# 1-Schematic_FFF_PCB_Connector.net
KiCad netlist of a schematic drawn in EasyEDA
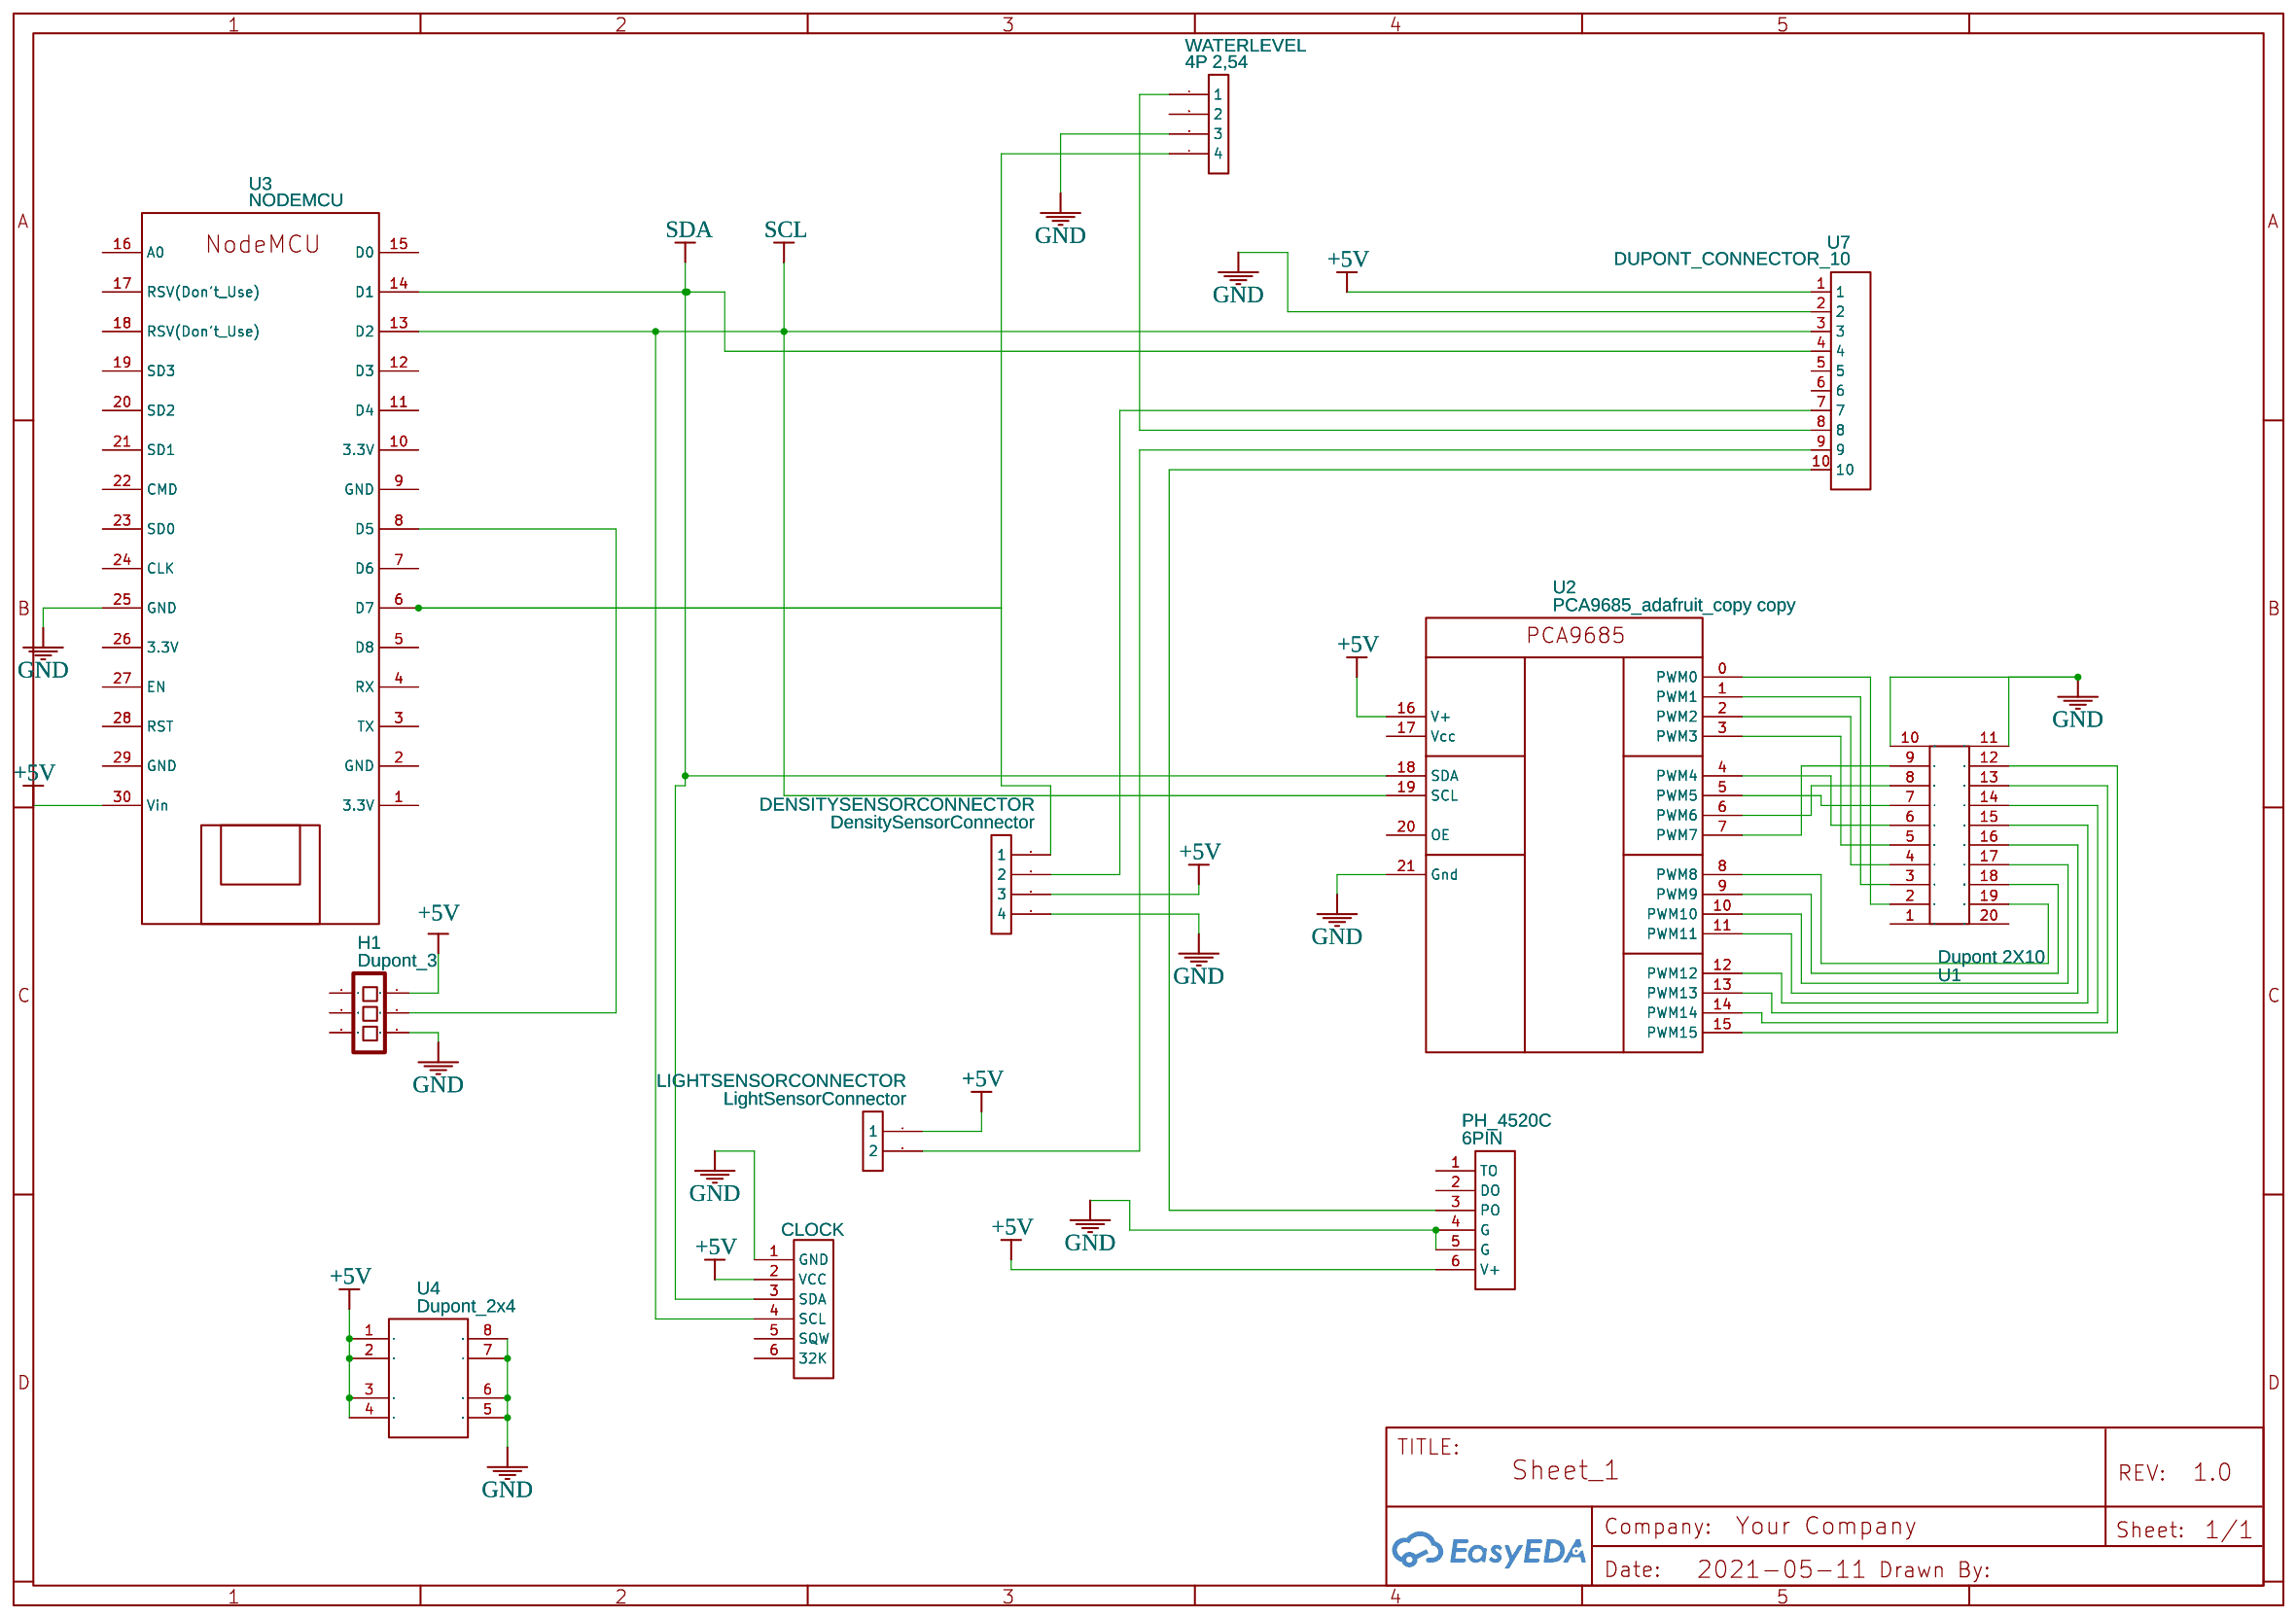
[diagram p0: schematic sheet]

(export (version "E")
  (design (tool "Eeschema 10.0.6"))
  (components
    (comp (ref "CLOCK") (value "6PIN") (libsource (lib "") (part "6PIN_1")))
    (comp (ref "DENSITYSENSORCONNECTOR")
      (value "DensitySensorConnector")
      (fields (field (name "BOM_Manufacturer Part") "Conector_dupont"))
      (libsource (lib "") (part "4P 2,54"))
    )
    (comp (ref "H1") (value "Dupont_3") (libsource (lib "") (part "Dupont_3")))
    (comp (ref "LIGHTSENSORCONNECTOR")
      (value "LightSensorConnector")
      (fields (field (name "BOM_Manufacturer Part") "Conector_dupont"))
      (libsource (lib "") (part "Dupont_1x2"))
    )
    (comp (ref "PH_4520C") (value "6PIN") (libsource (lib "") (part "6PIN")))
    (comp (ref "U1") (value "Dupont 2X10") (libsource (lib "") (part "Dupont 2X10")))
    (comp (ref "U2")
      (value "PCA9685_adafruit_copy copy")
      (libsource (lib "") (part "PCA9685_adafruit_copy copy"))
    )
    (comp (ref "U3") (value "NODEMCU") (libsource (lib "") (part "NODEMCU")))
    (comp (ref "U4")
      (value "Dupont_2x4")
      (fields (field (name "BOM_Manufacturer Part") "Custom"))
      (libsource (lib "") (part "Dupont_2x4"))
    )
    (comp (ref "U7") (value "DUPONT_CONNECTOR_10") (libsource (lib "") (part "DUPONT_CONNECTOR_10")))
    (comp (ref "WATERLEVEL")
      (value "4P 2,54")
      (fields (field (name "BOM_Manufacturer Part") "Conector_dupont"))
      (libsource (lib "") (part "4P 2,54_1"))
    )
  )
  (nets
    (net (code "1") (name "+5V") (class "Default")
      (node (ref "CLOCK") (pin "2") (pinfunction "VCC_2") (pintype "unspecified"))
      (node (ref "DENSITYSENSORCONNECTOR") (pin "3") (pinfunction "3_3") (pintype "unspecified"))
      (node (ref "H1") (pin "1") (pinfunction "1_1") (pintype "unspecified"))
      (node (ref "LIGHTSENSORCONNECTOR") (pin "1") (pinfunction "1_1") (pintype "unspecified"))
      (node (ref "PH_4520C") (pin "6") (pinfunction "V+_6") (pintype "unspecified"))
      (node (ref "U2") (pin "16") (pinfunction "V+_16") (pintype "unspecified"))
      (node (ref "U3") (pin "30") (pinfunction "Vin_30") (pintype "unspecified"))
      (node (ref "U4") (pin "1") (pinfunction "1_1") (pintype "unspecified"))
      (node (ref "U4") (pin "2") (pinfunction "2_2") (pintype "unspecified"))
      (node (ref "U4") (pin "3") (pinfunction "3_3") (pintype "unspecified"))
      (node (ref "U4") (pin "4") (pinfunction "4_4") (pintype "unspecified"))
      (node (ref "U7") (pin "1") (pinfunction "1_1") (pintype "unspecified"))
    )
    (net (code "2") (name "GND") (class "Default")
      (node (ref "CLOCK") (pin "1") (pinfunction "GND_1") (pintype "unspecified"))
      (node (ref "DENSITYSENSORCONNECTOR") (pin "4") (pinfunction "4_4") (pintype "unspecified"))
      (node (ref "H1") (pin "3") (pinfunction "3_3") (pintype "unspecified"))
      (node (ref "PH_4520C") (pin "4") (pinfunction "G_4") (pintype "unspecified"))
      (node (ref "PH_4520C") (pin "5") (pinfunction "G_5") (pintype "unspecified"))
      (node (ref "U1") (pin "10") (pinfunction "10_10") (pintype "unspecified"))
      (node (ref "U1") (pin "11") (pinfunction "1_11") (pintype "unspecified"))
      (node (ref "U2") (pin "21") (pinfunction "Gnd_21") (pintype "unspecified"))
      (node (ref "U3") (pin "25") (pinfunction "GND_25") (pintype "unspecified"))
      (node (ref "U4") (pin "5") (pinfunction "5_5") (pintype "unspecified"))
      (node (ref "U4") (pin "6") (pinfunction "6_6") (pintype "unspecified"))
      (node (ref "U4") (pin "7") (pinfunction "7_7") (pintype "unspecified"))
      (node (ref "U4") (pin "8") (pinfunction "8_8") (pintype "unspecified"))
      (node (ref "U7") (pin "2") (pinfunction "2_2") (pintype "unspecified"))
      (node (ref "WATERLEVEL") (pin "3") (pinfunction "3_3") (pintype "unspecified"))
    )
    (net (code "3") (name "Net-(DENSITYSENSORCONNECTOR-Pad2)") (class "Default")
      (node (ref "DENSITYSENSORCONNECTOR") (pin "2") (pinfunction "2_2") (pintype "unspecified"))
      (node (ref "U7") (pin "7") (pinfunction "7_7") (pintype "unspecified"))
    )
    (net (code "4") (name "Net-(LIGHTSENSORCONNECTOR-Pad2)") (class "Default")
      (node (ref "LIGHTSENSORCONNECTOR") (pin "2") (pinfunction "2_2") (pintype "unspecified"))
      (node (ref "U7") (pin "9") (pinfunction "9_9") (pintype "unspecified"))
    )
    (net (code "5") (name "Net-(PH_4520C-PO)") (class "Default")
      (node (ref "PH_4520C") (pin "3") (pinfunction "PO_3") (pintype "unspecified"))
      (node (ref "U7") (pin "10") (pinfunction "10_10") (pintype "unspecified"))
    )
    (net (code "6") (name "Net-(U2-PWM0)") (class "Default")
      (node (ref "U1") (pin "2") (pinfunction "2_2") (pintype "unspecified"))
      (node (ref "U2") (pin "0") (pinfunction "PWM0_0") (pintype "unspecified"))
    )
    (net (code "7") (name "Net-(U2-PWM1)") (class "Default")
      (node (ref "U1") (pin "3") (pinfunction "3_3") (pintype "unspecified"))
      (node (ref "U2") (pin "1") (pinfunction "PWM1_1") (pintype "unspecified"))
    )
    (net (code "8") (name "Net-(U2-PWM2)") (class "Default")
      (node (ref "U1") (pin "4") (pinfunction "4_4") (pintype "unspecified"))
      (node (ref "U2") (pin "2") (pinfunction "PWM2_2") (pintype "unspecified"))
    )
    (net (code "9") (name "Net-(U2-PWM3)") (class "Default")
      (node (ref "U1") (pin "5") (pinfunction "5_5") (pintype "unspecified"))
      (node (ref "U2") (pin "3") (pinfunction "PWM3_3") (pintype "unspecified"))
    )
    (net (code "10") (name "Net-(U2-PWM4)") (class "Default")
      (node (ref "U1") (pin "6") (pinfunction "6_6") (pintype "unspecified"))
      (node (ref "U2") (pin "4") (pinfunction "PWM4_4") (pintype "unspecified"))
    )
    (net (code "11") (name "Net-(U2-PWM5)") (class "Default")
      (node (ref "U1") (pin "7") (pinfunction "7_7") (pintype "unspecified"))
      (node (ref "U2") (pin "5") (pinfunction "PWM5_5") (pintype "unspecified"))
    )
    (net (code "12") (name "Net-(U2-PWM6)") (class "Default")
      (node (ref "U1") (pin "8") (pinfunction "8_8") (pintype "unspecified"))
      (node (ref "U2") (pin "6") (pinfunction "PWM6_6") (pintype "unspecified"))
    )
    (net (code "13") (name "Net-(U2-PWM7)") (class "Default")
      (node (ref "U1") (pin "9") (pinfunction "9_9") (pintype "unspecified"))
      (node (ref "U2") (pin "7") (pinfunction "PWM7_7") (pintype "unspecified"))
    )
    (net (code "14") (name "Net-(U2-PWM8)") (class "Default")
      (node (ref "U1") (pin "19") (pinfunction "9_19") (pintype "unspecified"))
      (node (ref "U2") (pin "8") (pinfunction "PWM8_8") (pintype "unspecified"))
    )
    (net (code "15") (name "Net-(U2-PWM9)") (class "Default")
      (node (ref "U1") (pin "18") (pinfunction "8_18") (pintype "unspecified"))
      (node (ref "U2") (pin "9") (pinfunction "PWM9_9") (pintype "unspecified"))
    )
    (net (code "16") (name "Net-(U2-PWM10)") (class "Default")
      (node (ref "U1") (pin "17") (pinfunction "7_17") (pintype "unspecified"))
      (node (ref "U2") (pin "10") (pinfunction "PWM10_10") (pintype "unspecified"))
    )
    (net (code "17") (name "Net-(U2-PWM11)") (class "Default")
      (node (ref "U1") (pin "16") (pinfunction "6_16") (pintype "unspecified"))
      (node (ref "U2") (pin "11") (pinfunction "PWM11_11") (pintype "unspecified"))
    )
    (net (code "18") (name "Net-(U2-PWM12)") (class "Default")
      (node (ref "U1") (pin "15") (pinfunction "5_15") (pintype "unspecified"))
      (node (ref "U2") (pin "12") (pinfunction "PWM12_12") (pintype "unspecified"))
    )
    (net (code "19") (name "Net-(U2-PWM13)") (class "Default")
      (node (ref "U1") (pin "14") (pinfunction "4_14") (pintype "unspecified"))
      (node (ref "U2") (pin "13") (pinfunction "PWM13_13") (pintype "unspecified"))
    )
    (net (code "20") (name "Net-(U2-PWM14)") (class "Default")
      (node (ref "U1") (pin "13") (pinfunction "3_13") (pintype "unspecified"))
      (node (ref "U2") (pin "14") (pinfunction "PWM14_14") (pintype "unspecified"))
    )
    (net (code "21") (name "Net-(U2-PWM15)") (class "Default")
      (node (ref "U1") (pin "12") (pinfunction "2_12") (pintype "unspecified"))
      (node (ref "U2") (pin "15") (pinfunction "PWM15_15") (pintype "unspecified"))
    )
    (net (code "22") (name "Net-(U3-D5)") (class "Default")
      (node (ref "H1") (pin "2") (pinfunction "2_2") (pintype "unspecified"))
      (node (ref "U3") (pin "8") (pinfunction "D5_8") (pintype "unspecified"))
    )
    (net (code "23") (name "Net-(U3-D7)") (class "Default")
      (node (ref "DENSITYSENSORCONNECTOR") (pin "1") (pinfunction "1_1") (pintype "unspecified"))
      (node (ref "U3") (pin "6") (pinfunction "D7_6") (pintype "unspecified"))
      (node (ref "WATERLEVEL") (pin "4") (pinfunction "4_4") (pintype "unspecified"))
    )
    (net (code "24") (name "Net-(U7-Pad8)") (class "Default")
      (node (ref "U7") (pin "8") (pinfunction "8_8") (pintype "unspecified"))
      (node (ref "WATERLEVEL") (pin "1") (pinfunction "1_1") (pintype "unspecified"))
    )
    (net (code "25") (name "SCL") (class "Default")
      (node (ref "CLOCK") (pin "4") (pinfunction "SCL_4") (pintype "unspecified"))
      (node (ref "U2") (pin "19") (pinfunction "SCL_19") (pintype "unspecified"))
      (node (ref "U3") (pin "13") (pinfunction "D2_13") (pintype "unspecified"))
      (node (ref "U7") (pin "3") (pinfunction "3_3") (pintype "unspecified"))
    )
    (net (code "26") (name "SDA") (class "Default")
      (node (ref "CLOCK") (pin "3") (pinfunction "SDA_3") (pintype "unspecified"))
      (node (ref "U2") (pin "18") (pinfunction "SDA_18") (pintype "unspecified"))
      (node (ref "U3") (pin "14") (pinfunction "D1_14") (pintype "unspecified"))
      (node (ref "U7") (pin "4") (pinfunction "4_4") (pintype "unspecified"))
    )
    (net (code "27") (name "unconnected-(CLOCK-32K-Pad6)") (class "Default")
      (node (ref "CLOCK") (pin "6") (pinfunction "32K_6") (pintype "unspecified"))
    )
    (net (code "28") (name "unconnected-(CLOCK-SQW-Pad5)") (class "Default")
      (node (ref "CLOCK") (pin "5") (pinfunction "SQW_5") (pintype "unspecified"))
    )
    (net (code "29") (name "unconnected-(H1-Pad1)") (class "Default")
      (node (ref "H1") (pin "1") (pinfunction "1_1") (pintype "unspecified"))
    )
    (net (code "30") (name "unconnected-(H1-Pad2)") (class "Default")
      (node (ref "H1") (pin "2") (pinfunction "2_2") (pintype "unspecified"))
    )
    (net (code "31") (name "unconnected-(H1-Pad3)") (class "Default")
      (node (ref "H1") (pin "3") (pinfunction "3_3") (pintype "unspecified"))
    )
    (net (code "32") (name "unconnected-(PH_4520C-DO-Pad2)") (class "Default")
      (node (ref "PH_4520C") (pin "2") (pinfunction "DO_2") (pintype "unspecified"))
    )
    (net (code "33") (name "unconnected-(PH_4520C-TO-Pad1)") (class "Default")
      (node (ref "PH_4520C") (pin "1") (pinfunction "TO_1") (pintype "unspecified"))
    )
    (net (code "34") (name "unconnected-(U1-10-Pad20)") (class "Default")
      (node (ref "U1") (pin "20") (pinfunction "10_20") (pintype "unspecified"))
    )
    (net (code "35") (name "unconnected-(U1-Pad1)") (class "Default")
      (node (ref "U1") (pin "1") (pinfunction "1_1") (pintype "unspecified"))
    )
    (net (code "36") (name "unconnected-(U2-OE-Pad20)") (class "Default")
      (node (ref "U2") (pin "20") (pinfunction "OE_20") (pintype "unspecified"))
    )
    (net (code "37") (name "unconnected-(U2-Vcc-Pad17)") (class "Default")
      (node (ref "U2") (pin "17") (pinfunction "Vcc_17") (pintype "unspecified"))
    )
    (net (code "38") (name "unconnected-(U3-3.3V-Pad1)") (class "Default")
      (node (ref "U3") (pin "1") (pinfunction "3.3V_1") (pintype "unspecified"))
    )
    (net (code "39") (name "unconnected-(U3-3.3V-Pad10)") (class "Default")
      (node (ref "U3") (pin "10") (pinfunction "3.3V_10") (pintype "unspecified"))
    )
    (net (code "40") (name "unconnected-(U3-3.3V-Pad26)") (class "Default")
      (node (ref "U3") (pin "26") (pinfunction "3.3V_26") (pintype "unspecified"))
    )
    (net (code "41") (name "unconnected-(U3-A0-Pad16)") (class "Default")
      (node (ref "U3") (pin "16") (pinfunction "A0_16") (pintype "unspecified"))
    )
    (net (code "42") (name "unconnected-(U3-CLK-Pad24)") (class "Default")
      (node (ref "U3") (pin "24") (pinfunction "CLK_24") (pintype "unspecified"))
    )
    (net (code "43") (name "unconnected-(U3-CMD-Pad22)") (class "Default")
      (node (ref "U3") (pin "22") (pinfunction "CMD_22") (pintype "unspecified"))
    )
    (net (code "44") (name "unconnected-(U3-D0-Pad15)") (class "Default")
      (node (ref "U3") (pin "15") (pinfunction "D0_15") (pintype "unspecified"))
    )
    (net (code "45") (name "unconnected-(U3-D3-Pad12)") (class "Default")
      (node (ref "U3") (pin "12") (pinfunction "D3_12") (pintype "unspecified"))
    )
    (net (code "46") (name "unconnected-(U3-D4-Pad11)") (class "Default")
      (node (ref "U3") (pin "11") (pinfunction "D4_11") (pintype "unspecified"))
    )
    (net (code "47") (name "unconnected-(U3-D6-Pad7)") (class "Default")
      (node (ref "U3") (pin "7") (pinfunction "D6_7") (pintype "unspecified"))
    )
    (net (code "48") (name "unconnected-(U3-D8-Pad5)") (class "Default")
      (node (ref "U3") (pin "5") (pinfunction "D8_5") (pintype "unspecified"))
    )
    (net (code "49") (name "unconnected-(U3-EN-Pad27)") (class "Default")
      (node (ref "U3") (pin "27") (pinfunction "EN_27") (pintype "unspecified"))
    )
    (net (code "50") (name "unconnected-(U3-GND-Pad2)") (class "Default")
      (node (ref "U3") (pin "2") (pinfunction "GND_2") (pintype "unspecified"))
    )
    (net (code "51") (name "unconnected-(U3-GND-Pad9)") (class "Default")
      (node (ref "U3") (pin "9") (pinfunction "GND_9") (pintype "unspecified"))
    )
    (net (code "52") (name "unconnected-(U3-GND-Pad29)") (class "Default")
      (node (ref "U3") (pin "29") (pinfunction "GND_29") (pintype "unspecified"))
    )
    (net (code "53") (name "unconnected-(U3-RST-Pad28)") (class "Default")
      (node (ref "U3") (pin "28") (pinfunction "RST_28") (pintype "unspecified"))
    )
    (net (code "54") (name "unconnected-(U3-RSV(Don't_Use)-Pad17)") (class "Default")
      (node (ref "U3") (pin "17") (pinfunction "RSV(Don't_Use)_17") (pintype "unspecified"))
    )
    (net (code "55") (name "unconnected-(U3-RSV(Don't_Use)-Pad18)") (class "Default")
      (node (ref "U3") (pin "18") (pinfunction "RSV(Don't_Use)_18") (pintype "unspecified"))
    )
    (net (code "56") (name "unconnected-(U3-RX-Pad4)") (class "Default")
      (node (ref "U3") (pin "4") (pinfunction "RX_4") (pintype "unspecified"))
    )
    (net (code "57") (name "unconnected-(U3-SD0-Pad23)") (class "Default")
      (node (ref "U3") (pin "23") (pinfunction "SD0_23") (pintype "unspecified"))
    )
    (net (code "58") (name "unconnected-(U3-SD1-Pad21)") (class "Default")
      (node (ref "U3") (pin "21") (pinfunction "SD1_21") (pintype "unspecified"))
    )
    (net (code "59") (name "unconnected-(U3-SD2-Pad20)") (class "Default")
      (node (ref "U3") (pin "20") (pinfunction "SD2_20") (pintype "unspecified"))
    )
    (net (code "60") (name "unconnected-(U3-SD3-Pad19)") (class "Default")
      (node (ref "U3") (pin "19") (pinfunction "SD3_19") (pintype "unspecified"))
    )
    (net (code "61") (name "unconnected-(U3-TX-Pad3)") (class "Default")
      (node (ref "U3") (pin "3") (pinfunction "TX_3") (pintype "unspecified"))
    )
    (net (code "62") (name "unconnected-(U7-Pad5)") (class "Default")
      (node (ref "U7") (pin "5") (pinfunction "5_5") (pintype "unspecified"))
    )
    (net (code "63") (name "unconnected-(U7-Pad6)") (class "Default")
      (node (ref "U7") (pin "6") (pinfunction "6_6") (pintype "unspecified"))
    )
    (net (code "64") (name "unconnected-(WATERLEVEL-Pad2)") (class "Default")
      (node (ref "WATERLEVEL") (pin "2") (pinfunction "2_2") (pintype "unspecified"))
    )
  )
)
